# gps-iridium-tracker.net
KiCad netlist of a schematic drawn in EAGLE
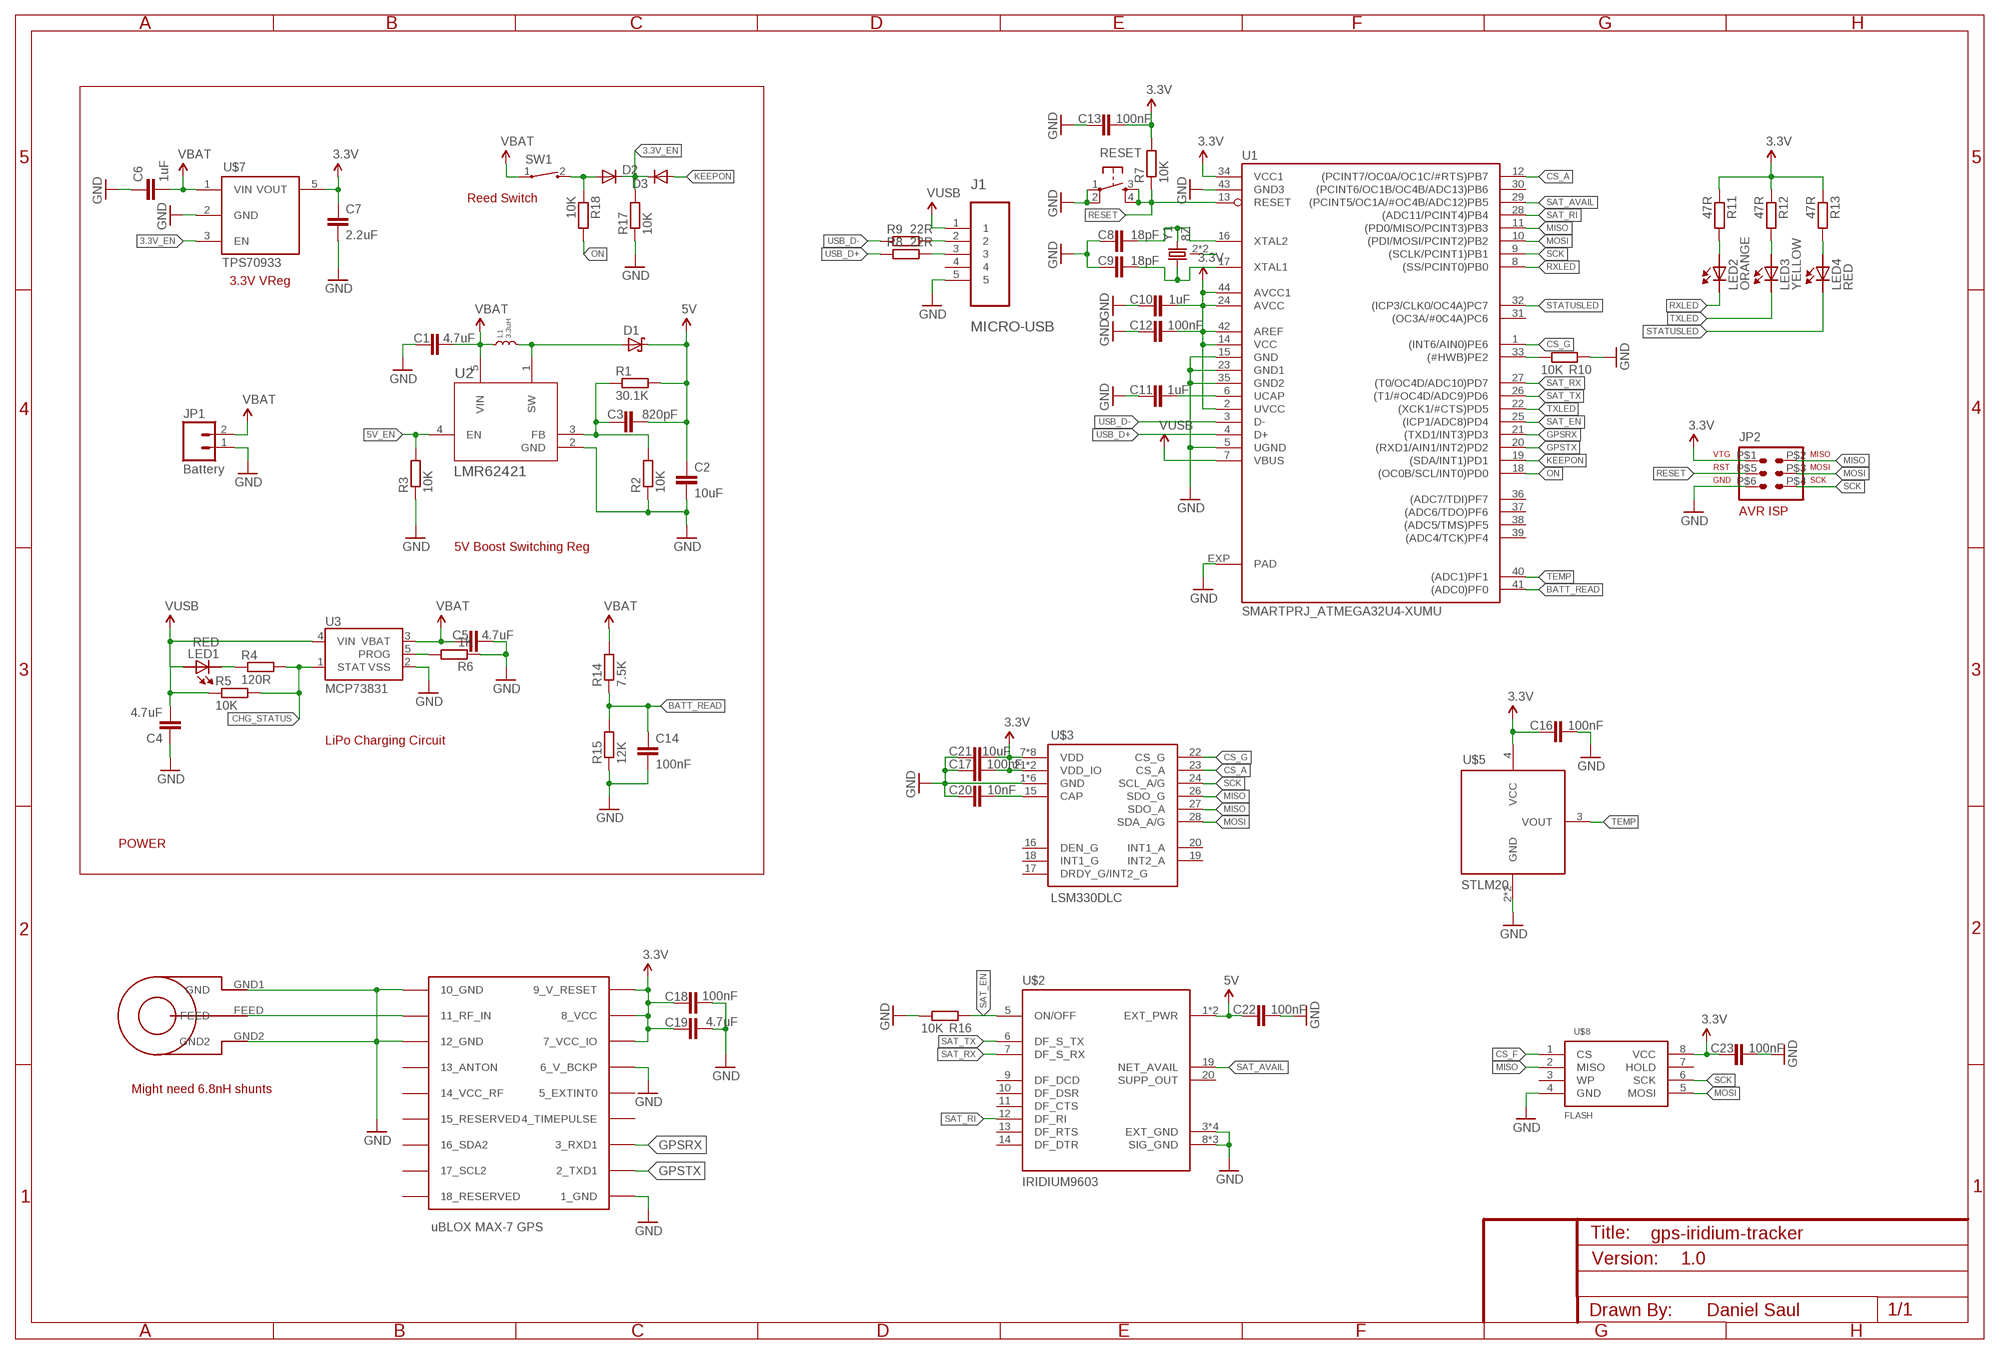
[diagram p0: schematic, sheet 1]

(export (version "E")
  (design (tool "Eeschema 10.0.6"))
  (components
    (comp (ref "C1")
      (value "4.7uF")
      (footprint "eagle-import:0603-CAP")
      (libsource (lib "eagle-import") (part "CAP0603-CAP"))
    )
    (comp (ref "C2")
      (value "10uF")
      (footprint "eagle-import:0603-CAP")
      (libsource (lib "eagle-import") (part "CAP0603-CAP"))
    )
    (comp (ref "C3")
      (value "820pF")
      (footprint "eagle-import:0603-CAP")
      (libsource (lib "eagle-import") (part "CAP0603-CAP"))
    )
    (comp (ref "C4")
      (value "4.7uF")
      (footprint "eagle-import:0603-CAP")
      (libsource (lib "eagle-import") (part "CAP0603-CAP"))
    )
    (comp (ref "C5")
      (value "4.7uF")
      (footprint "eagle-import:0603-CAP")
      (libsource (lib "eagle-import") (part "CAP0603-CAP"))
    )
    (comp (ref "C6")
      (value "1uF")
      (footprint "eagle-import:0603-CAP")
      (libsource (lib "eagle-import") (part "CAP0603-CAP"))
    )
    (comp (ref "C7")
      (value "2.2uF")
      (footprint "eagle-import:0603-CAP")
      (libsource (lib "eagle-import") (part "CAP0603-CAP"))
    )
    (comp (ref "C8")
      (value "18pF")
      (footprint "eagle-import:0603-CAP")
      (libsource (lib "eagle-import") (part "CAP0603-CAP"))
    )
    (comp (ref "C9")
      (value "18pF")
      (footprint "eagle-import:0603-CAP")
      (libsource (lib "eagle-import") (part "CAP0603-CAP"))
    )
    (comp (ref "C10")
      (value "1uF")
      (footprint "eagle-import:0402-CAP")
      (libsource (lib "eagle-import") (part "CAP0402-CAP"))
    )
    (comp (ref "C11")
      (value "1uF")
      (footprint "eagle-import:0402-CAP")
      (libsource (lib "eagle-import") (part "CAP0402-CAP"))
    )
    (comp (ref "C12")
      (value "100nF")
      (footprint "eagle-import:0402-CAP")
      (libsource (lib "eagle-import") (part "CAP0402-CAP"))
    )
    (comp (ref "C13")
      (value "100nF")
      (footprint "eagle-import:0402-CAP")
      (libsource (lib "eagle-import") (part "CAP0402-CAP"))
    )
    (comp (ref "C14")
      (value "100nF")
      (footprint "eagle-import:0402-CAP")
      (libsource (lib "eagle-import") (part "CAP0402-CAP"))
    )
    (comp (ref "C16")
      (value "100nF")
      (footprint "eagle-import:0402-CAP")
      (libsource (lib "eagle-import") (part "CAP0402-CAP"))
    )
    (comp (ref "C17")
      (value "100nF")
      (footprint "eagle-import:0402-CAP")
      (libsource (lib "eagle-import") (part "CAP0402-CAP"))
    )
    (comp (ref "C18")
      (value "100nF")
      (footprint "eagle-import:0402-CAP")
      (libsource (lib "eagle-import") (part "apex_CAP0402-CAP"))
    )
    (comp (ref "C19")
      (value "4.7uF")
      (footprint "eagle-import:0805")
      (libsource (lib "eagle-import") (part "apex_CAP0805"))
    )
    (comp (ref "C20")
      (value "10nF")
      (footprint "eagle-import:0402-CAP")
      (libsource (lib "eagle-import") (part "CAP0402-CAP"))
    )
    (comp (ref "C21")
      (value "10uF")
      (footprint "eagle-import:0402-CAP")
      (libsource (lib "eagle-import") (part "CAP0402-CAP"))
    )
    (comp (ref "C22")
      (value "100nF")
      (footprint "eagle-import:0402-CAP")
      (libsource (lib "eagle-import") (part "CAP0402-CAP"))
    )
    (comp (ref "C23")
      (value "100nF")
      (footprint "eagle-import:0402-CAP")
      (libsource (lib "eagle-import") (part "CAP0402-CAP"))
    )
    (comp (ref "D1")
      (value "B220A-13-F")
      (footprint "eagle-import:SMA-DIODE")
      (libsource (lib "eagle-import") (part "B220A-13-F"))
    )
    (comp (ref "D2")
      (value "DIODESOD")
      (footprint "eagle-import:SOD-323")
      (libsource (lib "eagle-import") (part "DIODESOD"))
    )
    (comp (ref "D3")
      (value "DIODESOD")
      (footprint "eagle-import:SOD-323")
      (libsource (lib "eagle-import") (part "DIODESOD"))
    )
    (comp (ref "GPS")
      (value "UBLOX_MAX-6")
      (footprint "eagle-import:UBLOX_MAX-6")
      (libsource (lib "eagle-import") (part "UBLOX_MAX-6"))
    )
    (comp (ref "J1")
      (value "MICRO-USB")
      (footprint "eagle-import:MOLEX_47346-0001")
      (fields (field (name "MPN") "47346-0001"))
      (libsource (lib "eagle-import") (part "47346-0001"))
    )
    (comp (ref "JP1")
      (value "Battery")
      (footprint "eagle-import:JST-2-PTH")
      (libsource (lib "eagle-import") (part "M02JST-PTH-2"))
    )
    (comp (ref "JP2")
      (value "AVR-ISP-6SMD")
      (footprint "eagle-import:ICSPSMD")
      (libsource (lib "eagle-import") (part "AVR-ISP-6SMD"))
    )
    (comp (ref "L1")
      (value "3.3uH")
      (footprint "eagle-import:SRN3015")
      (libsource (lib "eagle-import") (part "INDUCTOR-SRN3015"))
    )
    (comp (ref "LED1")
      (value "RED")
      (footprint "eagle-import:R0402")
      (libsource (lib "eagle-import") (part "LED"))
    )
    (comp (ref "LED2")
      (value "ORANGE")
      (footprint "eagle-import:R0402")
      (libsource (lib "eagle-import") (part "LED"))
    )
    (comp (ref "LED3")
      (value "YELLOW")
      (footprint "eagle-import:R0402")
      (libsource (lib "eagle-import") (part "LED"))
    )
    (comp (ref "LED4")
      (value "RED")
      (footprint "eagle-import:R0402")
      (libsource (lib "eagle-import") (part "LED"))
    )
    (comp (ref "R1")
      (value "30.1K")
      (footprint "eagle-import:R0402")
      (libsource (lib "eagle-import") (part "R-EU_R0402"))
    )
    (comp (ref "R2")
      (value "10K")
      (footprint "eagle-import:R0402")
      (libsource (lib "eagle-import") (part "R-EU_R0402"))
    )
    (comp (ref "R3")
      (value "10K")
      (footprint "eagle-import:R0402")
      (libsource (lib "eagle-import") (part "R-EU_R0402"))
    )
    (comp (ref "R4")
      (value "120R")
      (footprint "eagle-import:R0402")
      (libsource (lib "eagle-import") (part "R-EU_R0402"))
    )
    (comp (ref "R5")
      (value "10K")
      (footprint "eagle-import:R0402")
      (libsource (lib "eagle-import") (part "R-EU_R0402"))
    )
    (comp (ref "R6")
      (value "1K")
      (footprint "eagle-import:R0402")
      (libsource (lib "eagle-import") (part "R-EU_R0402"))
    )
    (comp (ref "R7")
      (value "10K")
      (footprint "eagle-import:R0402")
      (libsource (lib "eagle-import") (part "R-EU_R0402"))
    )
    (comp (ref "R8")
      (value "22R")
      (footprint "eagle-import:R0402")
      (libsource (lib "eagle-import") (part "R-EU_R0402"))
    )
    (comp (ref "R9")
      (value "22R")
      (footprint "eagle-import:R0402")
      (libsource (lib "eagle-import") (part "R-EU_R0402"))
    )
    (comp (ref "R10")
      (value "10K")
      (footprint "eagle-import:R0402")
      (libsource (lib "eagle-import") (part "R-EU_R0402"))
    )
    (comp (ref "R11")
      (value "47R")
      (footprint "eagle-import:R0402")
      (libsource (lib "eagle-import") (part "R-EU_R0402"))
    )
    (comp (ref "R12")
      (value "47R")
      (footprint "eagle-import:R0402")
      (libsource (lib "eagle-import") (part "R-EU_R0402"))
    )
    (comp (ref "R13")
      (value "47R")
      (footprint "eagle-import:R0402")
      (libsource (lib "eagle-import") (part "R-EU_R0402"))
    )
    (comp (ref "R14")
      (value "7.5K")
      (footprint "eagle-import:R0402")
      (libsource (lib "eagle-import") (part "R-EU_R0402"))
    )
    (comp (ref "R15")
      (value "12K")
      (footprint "eagle-import:R0402")
      (libsource (lib "eagle-import") (part "R-EU_R0402"))
    )
    (comp (ref "R16")
      (value "10K")
      (footprint "eagle-import:R0402")
      (libsource (lib "eagle-import") (part "R-EU_R0402"))
    )
    (comp (ref "R17")
      (value "10K")
      (footprint "eagle-import:R0402")
      (libsource (lib "eagle-import") (part "R-EU_R0402"))
    )
    (comp (ref "R18")
      (value "10K")
      (footprint "eagle-import:R0402")
      (libsource (lib "eagle-import") (part "R-EU_R0402"))
    )
    (comp (ref "RESET")
      (value "KMR441NGLFS")
      (footprint "eagle-import:KMR441NGLFS")
      (libsource (lib "eagle-import") (part "KMR441NGLFS"))
    )
    (comp (ref "SW1")
      (value "CT10-XXXX-G1")
      (footprint "eagle-import:CT10-XXXX-G1")
      (libsource (lib "eagle-import") (part "CT10-XXXX-G1"))
    )
    (comp (ref "U$1")
      (value "JTI_ANTENNA-1575AT54A0010")
      (footprint "eagle-import:JTI_ANTENNA-1575AT54A0010")
      (libsource (lib "eagle-import") (part "JTI_ANTENNA-1575AT54A0010"))
    )
    (comp (ref "U$2")
      (value "IRIDIUM9603")
      (footprint "eagle-import:IRIDIUM9603")
      (libsource (lib "eagle-import") (part "IRIDIUM9603"))
    )
    (comp (ref "U$3")
      (value "LSM330DLC")
      (footprint "eagle-import:LGA-28L")
      (libsource (lib "eagle-import") (part "LSM330DLC"))
    )
    (comp (ref "U$5")
      (value "STLM20")
      (footprint "eagle-import:SOT23-5L")
      (libsource (lib "eagle-import") (part "STLM20"))
    )
    (comp (ref "U$7")
      (value "TPS70933")
      (footprint "eagle-import:SOT23-5L")
      (libsource (lib "eagle-import") (part "TPS70933"))
    )
    (comp (ref "U$8")
      (value "FLASH")
      (footprint "eagle-import:SO08")
      (libsource (lib "eagle-import") (part "SPI_FLASH-X25XXSMD"))
    )
    (comp (ref "U1")
      (value "SMARTPRJ_ATMEGA32U4-XUMU")
      (footprint "eagle-import:SMARTPRJ_QFN44ML7X7")
      (libsource (lib "eagle-import") (part "SMARTPRJ_ATMEGA32U4-XUMU"))
    )
    (comp (ref "U2")
      (value "LMR62421")
      (footprint "eagle-import:MF05A")
      (fields
        (field (name "MANUFACTURER") "Texas Instruments")
        (field (name "MANUFACTURER_PART_NUMBER") "lmr62421_dbv_5")
      )
      (libsource (lib "eagle-import") (part "LMR62421_DBV_5"))
    )
    (comp (ref "U3")
      (value "MCP73831")
      (footprint "eagle-import:SOT23-5")
      (libsource (lib "eagle-import") (part "MCP73831"))
    )
    (comp (ref "Y1") (value "8Z") (footprint "eagle-import:8Z") (libsource (lib "eagle-import") (part "8Z")))
  )
  (nets
    (net (code "1") (name "3.3V") (class "Default")
      (node (ref "C10") (pin "2") (pinfunction "2_2") (pintype "passive"))
      (node (ref "C12") (pin "2") (pinfunction "2_2") (pintype "passive"))
      (node (ref "C13") (pin "2") (pinfunction "2_2") (pintype "passive"))
      (node (ref "C16") (pin "1") (pinfunction "1_1") (pintype "passive"))
      (node (ref "C17") (pin "2") (pinfunction "2_2") (pintype "passive"))
      (node (ref "C18") (pin "1") (pinfunction "1_1") (pintype "passive"))
      (node (ref "C19") (pin "1") (pinfunction "1_1") (pintype "passive"))
      (node (ref "C21") (pin "2") (pinfunction "2_2") (pintype "passive"))
      (node (ref "C23") (pin "1") (pinfunction "1_1") (pintype "passive"))
      (node (ref "C7") (pin "1") (pinfunction "1_1") (pintype "passive"))
      (node (ref "GPS") (pin "7_VCC_IO") (pinfunction "7_VCC_IO_7_VCC_IO") (pintype "power_in"))
      (node (ref "GPS") (pin "8_VCC") (pinfunction "8_VCC_8_VCC") (pintype "power_in"))
      (node (ref "GPS") (pin "9_V_RESET") (pinfunction "9_V_RESET_9_V_RESET") (pintype "power_in"))
      (node (ref "JP2") (pin "P$1") (pinfunction "2_P$1") (pintype "passive"))
      (node (ref "R11") (pin "1") (pinfunction "1_1") (pintype "passive"))
      (node (ref "R12") (pin "1") (pinfunction "1_1") (pintype "passive"))
      (node (ref "R13") (pin "1") (pinfunction "1_1") (pintype "passive"))
      (node (ref "R7") (pin "2") (pinfunction "2_2") (pintype "passive"))
      (node (ref "U$3") (pin "10") (pinfunction "VDD_10") (pintype "power_in"))
      (node (ref "U$3") (pin "11") (pinfunction "VDD_11") (pintype "power_in"))
      (node (ref "U$3") (pin "12") (pinfunction "VDD_12") (pintype "power_in"))
      (node (ref "U$3") (pin "13") (pinfunction "VDD_13") (pintype "power_in"))
      (node (ref "U$3") (pin "14") (pinfunction "VDD_14") (pintype "power_in"))
      (node (ref "U$3") (pin "21") (pinfunction "VDD_IO_21") (pintype "power_in"))
      (node (ref "U$3") (pin "25") (pinfunction "VDD_IO_25") (pintype "power_in"))
      (node (ref "U$3") (pin "7") (pinfunction "VDD_7") (pintype "power_in"))
      (node (ref "U$3") (pin "8") (pinfunction "VDD_8") (pintype "power_in"))
      (node (ref "U$3") (pin "9") (pinfunction "VDD_9") (pintype "power_in"))
      (node (ref "U$5") (pin "4") (pinfunction "VCC_4") (pintype "bidirectional"))
      (node (ref "U$7") (pin "5") (pinfunction "VOUT_5") (pintype "bidirectional"))
      (node (ref "U$8") (pin "8") (pinfunction "VCC_8") (pintype "bidirectional"))
      (node (ref "U1") (pin "14") (pinfunction "VCC_14") (pintype "power_in"))
      (node (ref "U1") (pin "2") (pinfunction "UVCC_2") (pintype "power_in"))
      (node (ref "U1") (pin "24") (pinfunction "AVCC_24") (pintype "power_in"))
      (node (ref "U1") (pin "34") (pinfunction "VCC1_34") (pintype "power_in"))
      (node (ref "U1") (pin "42") (pinfunction "AREF_42") (pintype "power_in"))
      (node (ref "U1") (pin "44") (pinfunction "AVCC1_44") (pintype "power_in"))
    )
    (net (code "2") (name "3.3V_EN") (class "Default")
      (node (ref "D2") (pin "1") (pinfunction "C_1") (pintype "passive"))
      (node (ref "D3") (pin "1") (pinfunction "C_1") (pintype "passive"))
      (node (ref "R17") (pin "2") (pinfunction "2_2") (pintype "passive"))
      (node (ref "U$7") (pin "3") (pinfunction "EN_3") (pintype "bidirectional"))
    )
    (net (code "3") (name "5V") (class "Default")
      (node (ref "C2") (pin "1") (pinfunction "1_1") (pintype "passive"))
      (node (ref "C22") (pin "1") (pinfunction "1_1") (pintype "passive"))
      (node (ref "C3") (pin "2") (pinfunction "2_2") (pintype "passive"))
      (node (ref "D1") (pin "2") (pinfunction "C_2") (pintype "passive"))
      (node (ref "R1") (pin "2") (pinfunction "2_2") (pintype "passive"))
      (node (ref "U$2") (pin "1") (pinfunction "EXT_PWR_1") (pintype "power_in"))
      (node (ref "U$2") (pin "2") (pinfunction "EXT_PWR_2") (pintype "power_in"))
    )
    (net (code "4") (name "5V_EN") (class "Default")
      (node (ref "R3") (pin "2") (pinfunction "2_2") (pintype "passive"))
      (node (ref "U2") (pin "4") (pinfunction "EN_4") (pintype "input"))
    )
    (net (code "5") (name "BATT_READ") (class "Default")
      (node (ref "C14") (pin "1") (pinfunction "1_1") (pintype "passive"))
      (node (ref "R14") (pin "1") (pinfunction "1_1") (pintype "passive"))
      (node (ref "R15") (pin "2") (pinfunction "2_2") (pintype "passive"))
      (node (ref "U1") (pin "41") (pinfunction "(ADC0)PF0_41") (pintype "bidirectional"))
    )
    (net (code "6") (name "CHG_STATUS") (class "Default")
      (node (ref "R4") (pin "2") (pinfunction "2_2") (pintype "passive"))
      (node (ref "R5") (pin "2") (pinfunction "2_2") (pintype "passive"))
      (node (ref "U3") (pin "1") (pinfunction "STAT_1") (pintype "output"))
    )
    (net (code "7") (name "CS_A") (class "Default")
      (node (ref "U$3") (pin "23") (pinfunction "CS_A_23") (pintype "input"))
      (node (ref "U1") (pin "12") (pinfunction "(PCINT7/OC0A/OC1C/#RTS)PB7_12") (pintype "bidirectional"))
    )
    (net (code "8") (name "CS_F") (class "Default")
      (node (ref "U$8") (pin "1") (pinfunction "CS_1") (pintype "bidirectional"))
    )
    (net (code "9") (name "CS_G") (class "Default")
      (node (ref "U$3") (pin "22") (pinfunction "CS_G_22") (pintype "input"))
      (node (ref "U1") (pin "1") (pinfunction "(INT6/AIN0)PE6_1") (pintype "bidirectional"))
    )
    (net (code "10") (name "GND") (class "Default")
      (node (ref "C1") (pin "1") (pinfunction "1_1") (pintype "passive"))
      (node (ref "C10") (pin "1") (pinfunction "1_1") (pintype "passive"))
      (node (ref "C11") (pin "1") (pinfunction "1_1") (pintype "passive"))
      (node (ref "C12") (pin "1") (pinfunction "1_1") (pintype "passive"))
      (node (ref "C13") (pin "1") (pinfunction "1_1") (pintype "passive"))
      (node (ref "C14") (pin "2") (pinfunction "2_2") (pintype "passive"))
      (node (ref "C16") (pin "2") (pinfunction "2_2") (pintype "passive"))
      (node (ref "C17") (pin "1") (pinfunction "1_1") (pintype "passive"))
      (node (ref "C18") (pin "2") (pinfunction "2_2") (pintype "passive"))
      (node (ref "C19") (pin "2") (pinfunction "2_2") (pintype "passive"))
      (node (ref "C2") (pin "2") (pinfunction "2_2") (pintype "passive"))
      (node (ref "C20") (pin "1") (pinfunction "1_1") (pintype "passive"))
      (node (ref "C21") (pin "1") (pinfunction "1_1") (pintype "passive"))
      (node (ref "C22") (pin "2") (pinfunction "2_2") (pintype "passive"))
      (node (ref "C23") (pin "2") (pinfunction "2_2") (pintype "passive"))
      (node (ref "C4") (pin "1") (pinfunction "1_1") (pintype "passive"))
      (node (ref "C5") (pin "2") (pinfunction "2_2") (pintype "passive"))
      (node (ref "C6") (pin "1") (pinfunction "1_1") (pintype "passive"))
      (node (ref "C7") (pin "2") (pinfunction "2_2") (pintype "passive"))
      (node (ref "C8") (pin "1") (pinfunction "1_1") (pintype "passive"))
      (node (ref "C9") (pin "1") (pinfunction "1_1") (pintype "passive"))
      (node (ref "GPS") (pin "10_GND") (pinfunction "10_GND_10_GND") (pintype "power_in"))
      (node (ref "GPS") (pin "12_GND") (pinfunction "12_GND_12_GND") (pintype "power_in"))
      (node (ref "GPS") (pin "1_GND") (pinfunction "1_GND_1_GND") (pintype "power_in"))
      (node (ref "GPS") (pin "6_V_BCKP") (pinfunction "6_V_BCKP_6_V_BCKP") (pintype "bidirectional"))
      (node (ref "J1") (pin "5") (pinfunction "5_5") (pintype "input"))
      (node (ref "JP1") (pin "1") (pinfunction "1_1") (pintype "passive"))
      (node (ref "JP2") (pin "P$6") (pinfunction "6_P$6") (pintype "passive"))
      (node (ref "R10") (pin "1") (pinfunction "1_1") (pintype "passive"))
      (node (ref "R15") (pin "1") (pinfunction "1_1") (pintype "passive"))
      (node (ref "R16") (pin "2") (pinfunction "2_2") (pintype "passive"))
      (node (ref "R17") (pin "1") (pinfunction "1_1") (pintype "passive"))
      (node (ref "R2") (pin "1") (pinfunction "1_1") (pintype "passive"))
      (node (ref "R3") (pin "1") (pinfunction "1_1") (pintype "passive"))
      (node (ref "R6") (pin "1") (pinfunction "1_1") (pintype "passive"))
      (node (ref "RESET") (pin "1") (pinfunction "P_1") (pintype "passive"))
      (node (ref "RESET") (pin "2") (pinfunction "P1_2") (pintype "passive"))
      (node (ref "U$1") (pin "GND1") (pinfunction "GND_GND1") (pintype "bidirectional"))
      (node (ref "U$1") (pin "GND2") (pinfunction "GND2_GND2") (pintype "bidirectional"))
      (node (ref "U$2") (pin "15") (pinfunction "SIG_GND_15") (pintype "power_in"))
      (node (ref "U$2") (pin "18") (pinfunction "SIG_GND_18") (pintype "power_in"))
      (node (ref "U$2") (pin "3") (pinfunction "EXT_GND_3") (pintype "power_in"))
      (node (ref "U$2") (pin "4") (pinfunction "EXT_GND_4") (pintype "power_in"))
      (node (ref "U$2") (pin "8") (pinfunction "SIG_GND_8") (pintype "power_in"))
      (node (ref "U$2") (pin "HOLE1") (pinfunction "EXT_GND_HOLE1") (pintype "power_in"))
      (node (ref "U$2") (pin "HOLE2") (pinfunction "EXT_GND_HOLE2") (pintype "power_in"))
      (node (ref "U$3") (pin "1") (pinfunction "GND_1") (pintype "power_in"))
      (node (ref "U$3") (pin "2") (pinfunction "GND_2") (pintype "power_in"))
      (node (ref "U$3") (pin "3") (pinfunction "GND_3") (pintype "power_in"))
      (node (ref "U$3") (pin "4") (pinfunction "GND_4") (pintype "power_in"))
      (node (ref "U$3") (pin "5") (pinfunction "GND_5") (pintype "power_in"))
      (node (ref "U$3") (pin "6") (pinfunction "GND_6") (pintype "power_in"))
      (node (ref "U$5") (pin "2") (pinfunction "GND_2") (pintype "bidirectional"))
      (node (ref "U$5") (pin "5") (pinfunction "GND_5") (pintype "bidirectional"))
      (node (ref "U$7") (pin "2") (pinfunction "GND_2") (pintype "bidirectional"))
      (node (ref "U$8") (pin "4") (pinfunction "GND_4") (pintype "bidirectional"))
      (node (ref "U1") (pin "15") (pinfunction "GND_15") (pintype "power_in"))
      (node (ref "U1") (pin "23") (pinfunction "GND1_23") (pintype "power_in"))
      (node (ref "U1") (pin "35") (pinfunction "GND2_35") (pintype "power_in"))
      (node (ref "U1") (pin "43") (pinfunction "GND3_43") (pintype "power_in"))
      (node (ref "U1") (pin "5") (pinfunction "UGND_5") (pintype "power_in"))
      (node (ref "U1") (pin "EXP") (pinfunction "PAD_EXP") (pintype "power_in"))
      (node (ref "U2") (pin "2") (pinfunction "GND_2") (pintype "power_in"))
      (node (ref "U3") (pin "2") (pinfunction "VSS_2") (pintype "power_in"))
      (node (ref "Y1") (pin "2") (pinfunction "GND_2") (pintype "bidirectional"))
      (node (ref "Y1") (pin "4") (pinfunction "GND_4") (pintype "bidirectional"))
    )
    (net (code "11") (name "GPSRX") (class "Default")
      (node (ref "GPS") (pin "3_RXD1") (pinfunction "3_RXD1_3_RXD1") (pintype "bidirectional"))
      (node (ref "U1") (pin "21") (pinfunction "(TXD1/INT3)PD3_21") (pintype "bidirectional"))
    )
    (net (code "12") (name "GPSTX") (class "Default")
      (node (ref "GPS") (pin "2_TXD1") (pinfunction "2_TXD1_2_TXD1") (pintype "bidirectional"))
      (node (ref "U1") (pin "20") (pinfunction "(RXD1/AIN1/INT2)PD2_20") (pintype "bidirectional"))
    )
    (net (code "13") (name "KEEPON") (class "Default")
      (node (ref "D3") (pin "2") (pinfunction "A_2") (pintype "passive"))
      (node (ref "U1") (pin "19") (pinfunction "(SDA/INT1)PD1_19") (pintype "bidirectional"))
    )
    (net (code "14") (name "MISO") (class "Default")
      (node (ref "JP2") (pin "P$2") (pinfunction "1_P$2") (pintype "passive"))
      (node (ref "U$3") (pin "26") (pinfunction "SDO_G_26") (pintype "output"))
      (node (ref "U$3") (pin "27") (pinfunction "SDO_A_27") (pintype "output"))
      (node (ref "U$8") (pin "2") (pinfunction "MISO_2") (pintype "bidirectional"))
      (node (ref "U1") (pin "11") (pinfunction "(PD0/MISO/PCINT3)PB3_11") (pintype "bidirectional"))
    )
    (net (code "15") (name "MOSI") (class "Default")
      (node (ref "JP2") (pin "P$3") (pinfunction "4_P$3") (pintype "passive"))
      (node (ref "U$3") (pin "28") (pinfunction "SDA_A/G_28") (pintype "input"))
      (node (ref "U$8") (pin "5") (pinfunction "MOSI_5") (pintype "bidirectional"))
      (node (ref "U1") (pin "10") (pinfunction "(PDI/MOSI/PCINT2)PB2_10") (pintype "bidirectional"))
    )
    (net (code "16") (name "Net-(D1-A)") (class "Default")
      (node (ref "D1") (pin "1") (pinfunction "A_1") (pintype "passive"))
      (node (ref "L1") (pin "2") (pinfunction "2_2") (pintype "passive"))
      (node (ref "U2") (pin "1") (pinfunction "SW_1") (pintype "passive"))
    )
    (net (code "17") (name "Net-(D2-A)") (class "Default")
      (node (ref "D2") (pin "2") (pinfunction "A_2") (pintype "passive"))
      (node (ref "R18") (pin "1") (pinfunction "1_1") (pintype "passive"))
      (node (ref "SW1") (pin "2") (pinfunction "2_2") (pintype "passive"))
    )
    (net (code "18") (name "Net-(GPS-Pad11_RF_IN)") (class "Default")
      (node (ref "GPS") (pin "11_RF_IN") (pinfunction "11_RF_IN_11_RF_IN") (pintype "bidirectional"))
      (node (ref "U$1") (pin "FEED") (pinfunction "FEED_FEED") (pintype "bidirectional"))
    )
    (net (code "19") (name "Net-(J1-Pad2)") (class "Default")
      (node (ref "J1") (pin "2") (pinfunction "2_2") (pintype "input"))
      (node (ref "R9") (pin "2") (pinfunction "2_2") (pintype "passive"))
    )
    (net (code "20") (name "Net-(J1-Pad3)") (class "Default")
      (node (ref "J1") (pin "3") (pinfunction "3_3") (pintype "input"))
      (node (ref "R8") (pin "2") (pinfunction "2_2") (pintype "passive"))
    )
    (net (code "21") (name "Net-(LED1-C)") (class "Default")
      (node (ref "LED1") (pin "1") (pinfunction "C_1") (pintype "passive"))
      (node (ref "R4") (pin "1") (pinfunction "1_1") (pintype "passive"))
    )
    (net (code "22") (name "Net-(LED2-A)") (class "Default")
      (node (ref "LED2") (pin "2") (pinfunction "A_2") (pintype "passive"))
      (node (ref "R11") (pin "2") (pinfunction "2_2") (pintype "passive"))
    )
    (net (code "23") (name "Net-(LED3-A)") (class "Default")
      (node (ref "LED3") (pin "2") (pinfunction "A_2") (pintype "passive"))
      (node (ref "R12") (pin "2") (pinfunction "2_2") (pintype "passive"))
    )
    (net (code "24") (name "Net-(LED4-A)") (class "Default")
      (node (ref "LED4") (pin "2") (pinfunction "A_2") (pintype "passive"))
      (node (ref "R13") (pin "2") (pinfunction "2_2") (pintype "passive"))
    )
    (net (code "25") (name "Net-(U$3-CAP)") (class "Default")
      (node (ref "C20") (pin "2") (pinfunction "2_2") (pintype "passive"))
      (node (ref "U$3") (pin "15") (pinfunction "CAP_15") (pintype "passive"))
    )
    (net (code "26") (name "Net-(U1-(#HWB)PE2)") (class "Default")
      (node (ref "R10") (pin "2") (pinfunction "2_2") (pintype "passive"))
      (node (ref "U1") (pin "33") (pinfunction "(#HWB)PE2_33") (pintype "bidirectional"))
    )
    (net (code "27") (name "Net-(U1-UCAP)") (class "Default")
      (node (ref "C11") (pin "2") (pinfunction "2_2") (pintype "passive"))
      (node (ref "U1") (pin "6") (pinfunction "UCAP_6") (pintype "passive"))
    )
    (net (code "28") (name "Net-(U1-XTAL1)") (class "Default")
      (node (ref "C9") (pin "2") (pinfunction "2_2") (pintype "passive"))
      (node (ref "U1") (pin "17") (pinfunction "XTAL1_17") (pintype "bidirectional"))
      (node (ref "Y1") (pin "1") (pinfunction "1_1") (pintype "passive"))
    )
    (net (code "29") (name "Net-(U1-XTAL2)") (class "Default")
      (node (ref "C8") (pin "2") (pinfunction "2_2") (pintype "passive"))
      (node (ref "U1") (pin "16") (pinfunction "XTAL2_16") (pintype "bidirectional"))
      (node (ref "Y1") (pin "3") (pinfunction "2_3") (pintype "passive"))
    )
    (net (code "30") (name "Net-(U2-FB)") (class "Default")
      (node (ref "C3") (pin "1") (pinfunction "1_1") (pintype "passive"))
      (node (ref "R1") (pin "1") (pinfunction "1_1") (pintype "passive"))
      (node (ref "R2") (pin "2") (pinfunction "2_2") (pintype "passive"))
      (node (ref "U2") (pin "3") (pinfunction "FB_3") (pintype "passive"))
    )
    (net (code "31") (name "Net-(U3-PROG)") (class "Default")
      (node (ref "R6") (pin "2") (pinfunction "2_2") (pintype "passive"))
      (node (ref "U3") (pin "5") (pinfunction "PROG_5") (pintype "input"))
    )
    (net (code "32") (name "ON") (class "Default")
      (node (ref "R18") (pin "2") (pinfunction "2_2") (pintype "passive"))
      (node (ref "U1") (pin "18") (pinfunction "(OC0B/SCL/INT0)PD0_18") (pintype "bidirectional"))
    )
    (net (code "33") (name "RESET") (class "Default")
      (node (ref "JP2") (pin "P$5") (pinfunction "5_P$5") (pintype "passive"))
      (node (ref "R7") (pin "1") (pinfunction "1_1") (pintype "passive"))
      (node (ref "RESET") (pin "3") (pinfunction "S_3") (pintype "passive"))
      (node (ref "RESET") (pin "4") (pinfunction "S1_4") (pintype "passive"))
      (node (ref "U1") (pin "13") (pinfunction "RESET_13") (pintype "input"))
    )
    (net (code "34") (name "RXLED") (class "Default")
      (node (ref "LED2") (pin "1") (pinfunction "C_1") (pintype "passive"))
      (node (ref "U1") (pin "8") (pinfunction "(SS/PCINT0)PB0_8") (pintype "bidirectional"))
    )
    (net (code "35") (name "SAT_AVAIL") (class "Default")
      (node (ref "U$2") (pin "19") (pinfunction "NET_AVAIL_19") (pintype "output"))
      (node (ref "U1") (pin "29") (pinfunction "(PCINT5/OC1A/#OC4B/ADC12)PB5_29") (pintype "bidirectional"))
    )
    (net (code "36") (name "SAT_EN") (class "Default")
      (node (ref "R16") (pin "1") (pinfunction "1_1") (pintype "passive"))
      (node (ref "U$2") (pin "5") (pinfunction "ON/OFF_5") (pintype "input"))
      (node (ref "U1") (pin "25") (pinfunction "(ICP1/ADC8)PD4_25") (pintype "bidirectional"))
    )
    (net (code "37") (name "SAT_RI") (class "Default")
      (node (ref "U$2") (pin "12") (pinfunction "DF_RI_12") (pintype "output"))
      (node (ref "U1") (pin "28") (pinfunction "(ADC11/PCINT4)PB4_28") (pintype "bidirectional"))
    )
    (net (code "38") (name "SAT_RX") (class "Default")
      (node (ref "U$2") (pin "7") (pinfunction "DF_S_RX_7") (pintype "output"))
      (node (ref "U1") (pin "27") (pinfunction "(T0/OC4D/ADC10)PD7_27") (pintype "bidirectional"))
    )
    (net (code "39") (name "SAT_TX") (class "Default")
      (node (ref "U$2") (pin "6") (pinfunction "DF_S_TX_6") (pintype "input"))
      (node (ref "U1") (pin "26") (pinfunction "(T1/#OC4D/ADC9)PD6_26") (pintype "bidirectional"))
    )
    (net (code "40") (name "SCK") (class "Default")
      (node (ref "JP2") (pin "P$4") (pinfunction "3_P$4") (pintype "passive"))
      (node (ref "U$3") (pin "24") (pinfunction "SCL_A/G_24") (pintype "input"))
      (node (ref "U$8") (pin "6") (pinfunction "SCK_6") (pintype "bidirectional"))
      (node (ref "U1") (pin "9") (pinfunction "(SCLK/PCINT1)PB1_9") (pintype "bidirectional"))
    )
    (net (code "41") (name "STATUSLED") (class "Default")
      (node (ref "LED4") (pin "1") (pinfunction "C_1") (pintype "passive"))
      (node (ref "U1") (pin "32") (pinfunction "(ICP3/CLK0/OC4A)PC7_32") (pintype "bidirectional"))
    )
    (net (code "42") (name "TEMP") (class "Default")
      (node (ref "U$5") (pin "3") (pinfunction "VOUT_3") (pintype "bidirectional"))
      (node (ref "U1") (pin "40") (pinfunction "(ADC1)PF1_40") (pintype "bidirectional"))
    )
    (net (code "43") (name "TXLED") (class "Default")
      (node (ref "LED3") (pin "1") (pinfunction "C_1") (pintype "passive"))
      (node (ref "U1") (pin "22") (pinfunction "(XCK1/#CTS)PD5_22") (pintype "bidirectional"))
    )
    (net (code "44") (name "USB_D+") (class "Default")
      (node (ref "R8") (pin "1") (pinfunction "1_1") (pintype "passive"))
      (node (ref "U1") (pin "4") (pinfunction "D+_4") (pintype "bidirectional"))
    )
    (net (code "45") (name "USB_D-") (class "Default")
      (node (ref "R9") (pin "1") (pinfunction "1_1") (pintype "passive"))
      (node (ref "U1") (pin "3") (pinfunction "D-_3") (pintype "bidirectional"))
    )
    (net (code "46") (name "VBAT") (class "Default")
      (node (ref "C1") (pin "2") (pinfunction "2_2") (pintype "passive"))
      (node (ref "C5") (pin "1") (pinfunction "1_1") (pintype "passive"))
      (node (ref "C6") (pin "2") (pinfunction "2_2") (pintype "passive"))
      (node (ref "JP1") (pin "2") (pinfunction "2_2") (pintype "passive"))
      (node (ref "L1") (pin "1") (pinfunction "1_1") (pintype "passive"))
      (node (ref "R14") (pin "2") (pinfunction "2_2") (pintype "passive"))
      (node (ref "SW1") (pin "1") (pinfunction "1_1") (pintype "passive"))
      (node (ref "U$7") (pin "1") (pinfunction "VIN_1") (pintype "bidirectional"))
      (node (ref "U2") (pin "5") (pinfunction "VIN_5") (pintype "input"))
      (node (ref "U3") (pin "3") (pinfunction "VBAT_3") (pintype "power_in"))
    )
    (net (code "47") (name "VUSB") (class "Default")
      (node (ref "C4") (pin "2") (pinfunction "2_2") (pintype "passive"))
      (node (ref "J1") (pin "1") (pinfunction "1_1") (pintype "input"))
      (node (ref "LED1") (pin "2") (pinfunction "A_2") (pintype "passive"))
      (node (ref "R5") (pin "1") (pinfunction "1_1") (pintype "passive"))
      (node (ref "U1") (pin "7") (pinfunction "VBUS_7") (pintype "input"))
      (node (ref "U3") (pin "4") (pinfunction "VIN_4") (pintype "power_in"))
    )
    (net (code "48") (name "unconnected-(GPS-Pad4_TIMEPULSE)") (class "Default")
      (node (ref "GPS") (pin "4_TIMEPULSE") (pinfunction "4_TIMEPULSE_4_TIMEPULSE") (pintype "bidirectional"))
    )
    (net (code "49") (name "unconnected-(GPS-Pad5_EXTINT0)") (class "Default")
      (node (ref "GPS") (pin "5_EXTINT0") (pinfunction "5_EXTINT0_5_EXTINT0") (pintype "bidirectional"))
    )
    (net (code "50") (name "unconnected-(GPS-Pad13_ANTON)") (class "Default")
      (node (ref "GPS") (pin "13_ANTON") (pinfunction "13_ANTON_13_ANTON") (pintype "bidirectional"))
    )
    (net (code "51") (name "unconnected-(GPS-Pad14_VCC_RF)") (class "Default")
      (node (ref "GPS") (pin "14_VCC_RF") (pinfunction "14_VCC_RF_14_VCC_RF") (pintype "bidirectional"))
    )
    (net (code "52") (name "unconnected-(GPS-Pad15_RESERVED)") (class "Default")
      (node (ref "GPS") (pin "15_RESERVED") (pinfunction "15_RESERVED_15_RESERVED") (pintype "bidirectional"))
    )
    (net (code "53") (name "unconnected-(GPS-Pad16_SDA2)") (class "Default")
      (node (ref "GPS") (pin "16_SDA2") (pinfunction "16_SDA2_16_SDA2") (pintype "bidirectional"))
    )
    (net (code "54") (name "unconnected-(GPS-Pad17_SCL2)") (class "Default")
      (node (ref "GPS") (pin "17_SCL2") (pinfunction "17_SCL2_17_SCL2") (pintype "bidirectional"))
    )
    (net (code "55") (name "unconnected-(GPS-Pad18_RESERVED)") (class "Default")
      (node (ref "GPS") (pin "18_RESERVED") (pinfunction "18_RESERVED_18_RESERVED") (pintype "bidirectional"))
    )
    (net (code "56") (name "unconnected-(J1-Pad4)") (class "Default")
      (node (ref "J1") (pin "4") (pinfunction "4_4") (pintype "input"))
    )
    (net (code "57") (name "unconnected-(U$2-DF_CTS-Pad11)") (class "Default")
      (node (ref "U$2") (pin "11") (pinfunction "DF_CTS_11") (pintype "output"))
    )
    (net (code "58") (name "unconnected-(U$2-DF_DCD-Pad9)") (class "Default")
      (node (ref "U$2") (pin "9") (pinfunction "DF_DCD_9") (pintype "output"))
    )
    (net (code "59") (name "unconnected-(U$2-DF_DSR-Pad10)") (class "Default")
      (node (ref "U$2") (pin "10") (pinfunction "DF_DSR_10") (pintype "output"))
    )
    (net (code "60") (name "unconnected-(U$2-DF_DTR-Pad14)") (class "Default")
      (node (ref "U$2") (pin "14") (pinfunction "DF_DTR_14") (pintype "input"))
    )
    (net (code "61") (name "unconnected-(U$2-DF_RTS-Pad13)") (class "Default")
      (node (ref "U$2") (pin "13") (pinfunction "DF_RTS_13") (pintype "input"))
    )
    (net (code "62") (name "unconnected-(U$2-SUPP_OUT-Pad20)") (class "Default")
      (node (ref "U$2") (pin "20") (pinfunction "SUPP_OUT_20") (pintype "output"))
    )
    (net (code "63") (name "unconnected-(U$3-DEN_G-Pad16)") (class "Default")
      (node (ref "U$3") (pin "16") (pinfunction "DEN_G_16") (pintype "input"))
    )
    (net (code "64") (name "unconnected-(U$3-DRDY_G{slash}INT2_G-Pad17)") (class "Default")
      (node (ref "U$3") (pin "17") (pinfunction "DRDY_G/INT2_G_17") (pintype "output"))
    )
    (net (code "65") (name "unconnected-(U$3-INT1_A-Pad20)") (class "Default")
      (node (ref "U$3") (pin "20") (pinfunction "INT1_A_20") (pintype "output"))
    )
    (net (code "66") (name "unconnected-(U$3-INT1_G-Pad18)") (class "Default")
      (node (ref "U$3") (pin "18") (pinfunction "INT1_G_18") (pintype "output"))
    )
    (net (code "67") (name "unconnected-(U$3-INT2_A-Pad19)") (class "Default")
      (node (ref "U$3") (pin "19") (pinfunction "INT2_A_19") (pintype "output"))
    )
    (net (code "68") (name "unconnected-(U$8-HOLD-Pad7)") (class "Default")
      (node (ref "U$8") (pin "7") (pinfunction "HOLD_7") (pintype "bidirectional"))
    )
    (net (code "69") (name "unconnected-(U$8-WP-Pad3)") (class "Default")
      (node (ref "U$8") (pin "3") (pinfunction "WP_3") (pintype "bidirectional"))
    )
    (net (code "70") (name "unconnected-(U1-(ADC4{slash}TCK)PF4-Pad39)") (class "Default")
      (node (ref "U1") (pin "39") (pinfunction "(ADC4/TCK)PF4_39") (pintype "bidirectional"))
    )
    (net (code "71") (name "unconnected-(U1-(ADC5{slash}TMS)PF5-Pad38)") (class "Default")
      (node (ref "U1") (pin "38") (pinfunction "(ADC5/TMS)PF5_38") (pintype "bidirectional"))
    )
    (net (code "72") (name "unconnected-(U1-(ADC6{slash}TDO)PF6-Pad37)") (class "Default")
      (node (ref "U1") (pin "37") (pinfunction "(ADC6/TDO)PF6_37") (pintype "bidirectional"))
    )
    (net (code "73") (name "unconnected-(U1-(ADC7{slash}TDI)PF7-Pad36)") (class "Default")
      (node (ref "U1") (pin "36") (pinfunction "(ADC7/TDI)PF7_36") (pintype "bidirectional"))
    )
    (net (code "74") (name "unconnected-(U1-(OC3A{slash}#0C4A)PC6-Pad31)") (class "Default")
      (node (ref "U1") (pin "31") (pinfunction "(OC3A/#0C4A)PC6_31") (pintype "bidirectional"))
    )
    (net (code "75") (name "unconnected-(U1-(PCINT6{slash}OC1B{slash}OC4B{slash}ADC13)PB6-Pad30)") (class "Default")
      (node (ref "U1") (pin "30") (pinfunction "(PCINT6/OC1B/OC4B/ADC13)PB6_30") (pintype "bidirectional"))
    )
  )
)
